# DISPLAY.net
KiCad netlist of a schematic drawn in Altium Designer
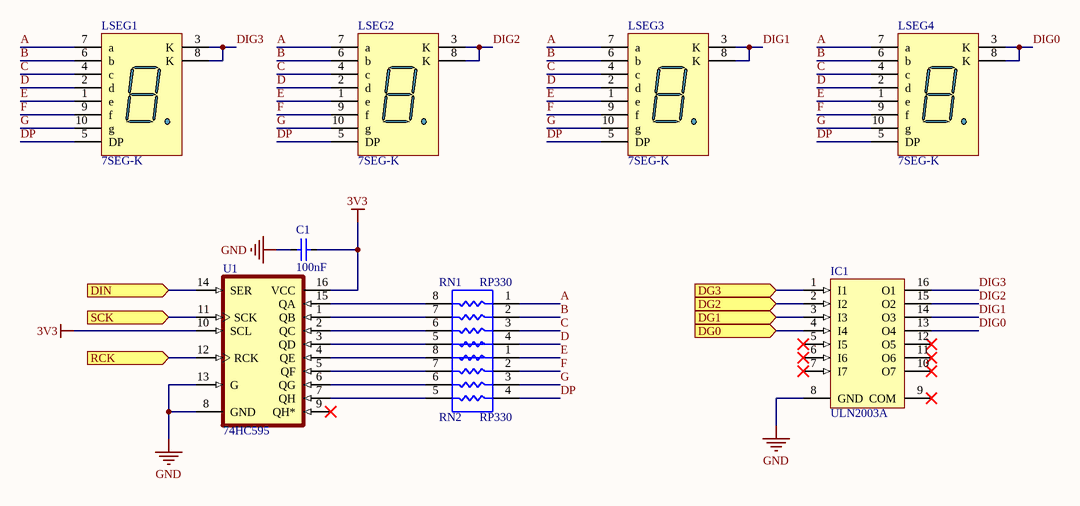
[diagram p0: DISPLAY.SchDoc]

(export (version "E")
  (design (tool "Eeschema 10.0.6"))
  (components
    (comp (ref "C1")
      (value "100nF")
      (footprint "CAP_0805")
      (description "Capacitor")
      (fields (field (name "PUBLISHER") "Altium Limited"))
      (libsource (lib "My Library") (part "CapSMD"))
    )
    (comp (ref "IC1")
      (value "ULN2003A")
      (footprint "SOIC16")
      (description "High-Voltage, High-Current Darlington Array")
      (fields (field (name "PUBLISHER") "Altium Limited"))
      (libsource (lib "My Library") (part "ULN2003A"))
    )
    (comp (ref "LSEG1")
      (value "7SEG-K")
      (footprint "LED7SEG")
      (description "14.2 mm General Purpose Blue 7-Segment Display: CC, RH DP, Gray Surface")
      (fields (field (name "PUBLISHER") "Altium Limited"))
      (libsource (lib "My Library") (part "LED7SEG-K"))
    )
    (comp (ref "LSEG2")
      (value "7SEG-K")
      (footprint "LED7SEG")
      (description "14.2 mm General Purpose Blue 7-Segment Display: CC, RH DP, Gray Surface")
      (fields (field (name "PUBLISHER") "Altium Limited"))
      (libsource (lib "My Library") (part "LED7SEG-K"))
    )
    (comp (ref "LSEG3")
      (value "7SEG-K")
      (footprint "LED7SEG")
      (description "14.2 mm General Purpose Blue 7-Segment Display: CC, RH DP, Gray Surface")
      (fields (field (name "PUBLISHER") "Altium Limited"))
      (libsource (lib "My Library") (part "LED7SEG-K"))
    )
    (comp (ref "LSEG4")
      (value "7SEG-K")
      (footprint "LED7SEG")
      (description "14.2 mm General Purpose Blue 7-Segment Display: CC, RH DP, Gray Surface")
      (fields (field (name "PUBLISHER") "Altium Limited"))
      (libsource (lib "My Library") (part "LED7SEG-K"))
    )
    (comp (ref "RN1") (value "RP330") (footprint "RN4-0805") (libsource (lib "My Library") (part "RN4-Dual")))
    (comp (ref "RN2") (value "RP330") (footprint "RN4-0805") (libsource (lib "My Library") (part "RN4-Dual")))
    (comp (ref "U1")
      (value "74HC595")
      (footprint "SOIC16")
      (description "8-bit Serial-Input/Serial or Parallel Output Shift Register with Latched 3-state Outputs")
      (libsource (lib "My Library") (part "74HC595"))
    )
  )
  (nets
    (net (code "1") (name "/A") (class "Default")
      (node (ref "LSEG1") (pin "7") (pinfunction "a_7") (pintype "passive"))
      (node (ref "LSEG2") (pin "7") (pinfunction "a_7") (pintype "passive"))
      (node (ref "LSEG3") (pin "7") (pinfunction "a_7") (pintype "passive"))
      (node (ref "LSEG4") (pin "7") (pinfunction "a_7") (pintype "passive"))
      (node (ref "RN1") (pin "1") (pinfunction "1_1") (pintype "passive"))
    )
    (net (code "2") (name "/B") (class "Default")
      (node (ref "LSEG1") (pin "6") (pinfunction "b_6") (pintype "passive"))
      (node (ref "LSEG2") (pin "6") (pinfunction "b_6") (pintype "passive"))
      (node (ref "LSEG3") (pin "6") (pinfunction "b_6") (pintype "passive"))
      (node (ref "LSEG4") (pin "6") (pinfunction "b_6") (pintype "passive"))
      (node (ref "RN1") (pin "2") (pinfunction "2_2") (pintype "passive"))
    )
    (net (code "3") (name "/C") (class "Default")
      (node (ref "LSEG1") (pin "4") (pinfunction "c_4") (pintype "passive"))
      (node (ref "LSEG2") (pin "4") (pinfunction "c_4") (pintype "passive"))
      (node (ref "LSEG3") (pin "4") (pinfunction "c_4") (pintype "passive"))
      (node (ref "LSEG4") (pin "4") (pinfunction "c_4") (pintype "passive"))
      (node (ref "RN1") (pin "3") (pinfunction "3_3") (pintype "passive"))
    )
    (net (code "4") (name "/D") (class "Default")
      (node (ref "LSEG1") (pin "2") (pinfunction "d_2") (pintype "passive"))
      (node (ref "LSEG2") (pin "2") (pinfunction "d_2") (pintype "passive"))
      (node (ref "LSEG3") (pin "2") (pinfunction "d_2") (pintype "passive"))
      (node (ref "LSEG4") (pin "2") (pinfunction "d_2") (pintype "passive"))
      (node (ref "RN1") (pin "4") (pinfunction "4_4") (pintype "passive"))
    )
    (net (code "5") (name "/DG0") (class "Default")
      (node (ref "IC1") (pin "4") (pinfunction "I4_4") (pintype "input"))
    )
    (net (code "6") (name "/DG1") (class "Default")
      (node (ref "IC1") (pin "3") (pinfunction "I3_3") (pintype "input"))
    )
    (net (code "7") (name "/DG2") (class "Default")
      (node (ref "IC1") (pin "2") (pinfunction "I2_2") (pintype "input"))
    )
    (net (code "8") (name "/DG3") (class "Default")
      (node (ref "IC1") (pin "1") (pinfunction "I1_1") (pintype "input"))
    )
    (net (code "9") (name "/DIG0") (class "Default")
      (node (ref "IC1") (pin "13") (pinfunction "O4_13") (pintype "open_collector"))
      (node (ref "LSEG4") (pin "3") (pinfunction "K_3") (pintype "passive"))
      (node (ref "LSEG4") (pin "8") (pinfunction "K_8") (pintype "passive"))
    )
    (net (code "10") (name "/DIG1") (class "Default")
      (node (ref "IC1") (pin "14") (pinfunction "O3_14") (pintype "open_collector"))
      (node (ref "LSEG3") (pin "3") (pinfunction "K_3") (pintype "passive"))
      (node (ref "LSEG3") (pin "8") (pinfunction "K_8") (pintype "passive"))
    )
    (net (code "11") (name "/DIG2") (class "Default")
      (node (ref "IC1") (pin "15") (pinfunction "O2_15") (pintype "open_collector"))
      (node (ref "LSEG2") (pin "3") (pinfunction "K_3") (pintype "passive"))
      (node (ref "LSEG2") (pin "8") (pinfunction "K_8") (pintype "passive"))
    )
    (net (code "12") (name "/DIG3") (class "Default")
      (node (ref "IC1") (pin "16") (pinfunction "O1_16") (pintype "open_collector"))
      (node (ref "LSEG1") (pin "3") (pinfunction "K_3") (pintype "passive"))
      (node (ref "LSEG1") (pin "8") (pinfunction "K_8") (pintype "passive"))
    )
    (net (code "13") (name "/DIN") (class "Default")
      (node (ref "U1") (pin "14") (pinfunction "SER_14") (pintype "input"))
    )
    (net (code "14") (name "/DP") (class "Default")
      (node (ref "LSEG1") (pin "5") (pinfunction "DP_5") (pintype "passive"))
      (node (ref "LSEG2") (pin "5") (pinfunction "DP_5") (pintype "passive"))
      (node (ref "LSEG3") (pin "5") (pinfunction "DP_5") (pintype "passive"))
      (node (ref "LSEG4") (pin "5") (pinfunction "DP_5") (pintype "passive"))
      (node (ref "RN2") (pin "4") (pinfunction "4_4") (pintype "passive"))
    )
    (net (code "15") (name "/E") (class "Default")
      (node (ref "LSEG1") (pin "1") (pinfunction "e_1") (pintype "passive"))
      (node (ref "LSEG2") (pin "1") (pinfunction "e_1") (pintype "passive"))
      (node (ref "LSEG3") (pin "1") (pinfunction "e_1") (pintype "passive"))
      (node (ref "LSEG4") (pin "1") (pinfunction "e_1") (pintype "passive"))
      (node (ref "RN2") (pin "1") (pinfunction "1_1") (pintype "passive"))
    )
    (net (code "16") (name "/F") (class "Default")
      (node (ref "LSEG1") (pin "9") (pinfunction "f_9") (pintype "passive"))
      (node (ref "LSEG2") (pin "9") (pinfunction "f_9") (pintype "passive"))
      (node (ref "LSEG3") (pin "9") (pinfunction "f_9") (pintype "passive"))
      (node (ref "LSEG4") (pin "9") (pinfunction "f_9") (pintype "passive"))
      (node (ref "RN2") (pin "2") (pinfunction "2_2") (pintype "passive"))
    )
    (net (code "17") (name "/G") (class "Default")
      (node (ref "LSEG1") (pin "10") (pinfunction "g_10") (pintype "passive"))
      (node (ref "LSEG2") (pin "10") (pinfunction "g_10") (pintype "passive"))
      (node (ref "LSEG3") (pin "10") (pinfunction "g_10") (pintype "passive"))
      (node (ref "LSEG4") (pin "10") (pinfunction "g_10") (pintype "passive"))
      (node (ref "RN2") (pin "3") (pinfunction "3_3") (pintype "passive"))
    )
    (net (code "18") (name "/RCK") (class "Default")
      (node (ref "U1") (pin "12") (pinfunction "RCK_12") (pintype "input"))
    )
    (net (code "19") (name "/SCK") (class "Default")
      (node (ref "U1") (pin "11") (pinfunction "SCK_11") (pintype "input"))
    )
    (net (code "20") (name "3V3") (class "Default")
      (node (ref "C1") (pin "1") (pinfunction "1_1") (pintype "passive"))
      (node (ref "U1") (pin "10") (pinfunction "SCL_10") (pintype "input"))
      (node (ref "U1") (pin "16") (pinfunction "VCC_16") (pintype "power_in"))
    )
    (net (code "21") (name "GND") (class "Default")
      (node (ref "C1") (pin "2") (pinfunction "2_2") (pintype "passive"))
      (node (ref "IC1") (pin "8") (pinfunction "GND_8") (pintype "power_in"))
      (node (ref "U1") (pin "13") (pinfunction "G_13") (pintype "input"))
      (node (ref "U1") (pin "8") (pinfunction "GND_8") (pintype "power_in"))
    )
    (net (code "22") (name "Net-(U1-QA)") (class "Default")
      (node (ref "RN1") (pin "8") (pinfunction "8_8") (pintype "passive"))
      (node (ref "U1") (pin "15") (pinfunction "QA_15") (pintype "input"))
    )
    (net (code "23") (name "Net-(U1-QB)") (class "Default")
      (node (ref "RN1") (pin "7") (pinfunction "7_7") (pintype "passive"))
      (node (ref "U1") (pin "1") (pinfunction "QB_1") (pintype "input"))
    )
    (net (code "24") (name "Net-(U1-QC)") (class "Default")
      (node (ref "RN1") (pin "6") (pinfunction "6_6") (pintype "passive"))
      (node (ref "U1") (pin "2") (pinfunction "QC_2") (pintype "input"))
    )
    (net (code "25") (name "Net-(U1-QD)") (class "Default")
      (node (ref "RN1") (pin "5") (pinfunction "5_5") (pintype "passive"))
      (node (ref "U1") (pin "3") (pinfunction "QD_3") (pintype "input"))
    )
    (net (code "26") (name "Net-(U1-QE)") (class "Default")
      (node (ref "RN2") (pin "8") (pinfunction "8_8") (pintype "passive"))
      (node (ref "U1") (pin "4") (pinfunction "QE_4") (pintype "input"))
    )
    (net (code "27") (name "Net-(U1-QF)") (class "Default")
      (node (ref "RN2") (pin "7") (pinfunction "7_7") (pintype "passive"))
      (node (ref "U1") (pin "5") (pinfunction "QF_5") (pintype "input"))
    )
    (net (code "28") (name "Net-(U1-QG)") (class "Default")
      (node (ref "RN2") (pin "6") (pinfunction "6_6") (pintype "passive"))
      (node (ref "U1") (pin "6") (pinfunction "QG_6") (pintype "input"))
    )
    (net (code "29") (name "Net-(U1-QH)") (class "Default")
      (node (ref "RN2") (pin "5") (pinfunction "5_5") (pintype "passive"))
      (node (ref "U1") (pin "7") (pinfunction "QH_7") (pintype "input"))
    )
    (net (code "30") (name "unconnected-(IC1-COM-Pad9)") (class "Default")
      (node (ref "IC1") (pin "9") (pinfunction "COM_9") (pintype "passive+no_connect"))
    )
    (net (code "31") (name "unconnected-(IC1-I5-Pad5)") (class "Default")
      (node (ref "IC1") (pin "5") (pinfunction "I5_5") (pintype "input+no_connect"))
    )
    (net (code "32") (name "unconnected-(IC1-I6-Pad6)") (class "Default")
      (node (ref "IC1") (pin "6") (pinfunction "I6_6") (pintype "input+no_connect"))
    )
    (net (code "33") (name "unconnected-(IC1-I7-Pad7)") (class "Default")
      (node (ref "IC1") (pin "7") (pinfunction "I7_7") (pintype "input+no_connect"))
    )
    (net (code "34") (name "unconnected-(IC1-O5-Pad12)") (class "Default")
      (node (ref "IC1") (pin "12") (pinfunction "O5_12") (pintype "open_collector+no_connect"))
    )
    (net (code "35") (name "unconnected-(IC1-O6-Pad11)") (class "Default")
      (node (ref "IC1") (pin "11") (pinfunction "O6_11") (pintype "open_collector+no_connect"))
    )
    (net (code "36") (name "unconnected-(IC1-O7-Pad10)") (class "Default")
      (node (ref "IC1") (pin "10") (pinfunction "O7_10") (pintype "open_collector+no_connect"))
    )
    (net (code "37") (name "unconnected-(U1-QH*-Pad9)") (class "Default")
      (node (ref "U1") (pin "9") (pinfunction "QH*_9") (pintype "input+no_connect"))
    )
  )
)
